# PCB.net
KiCad netlist of a schematic drawn in Altium Designer
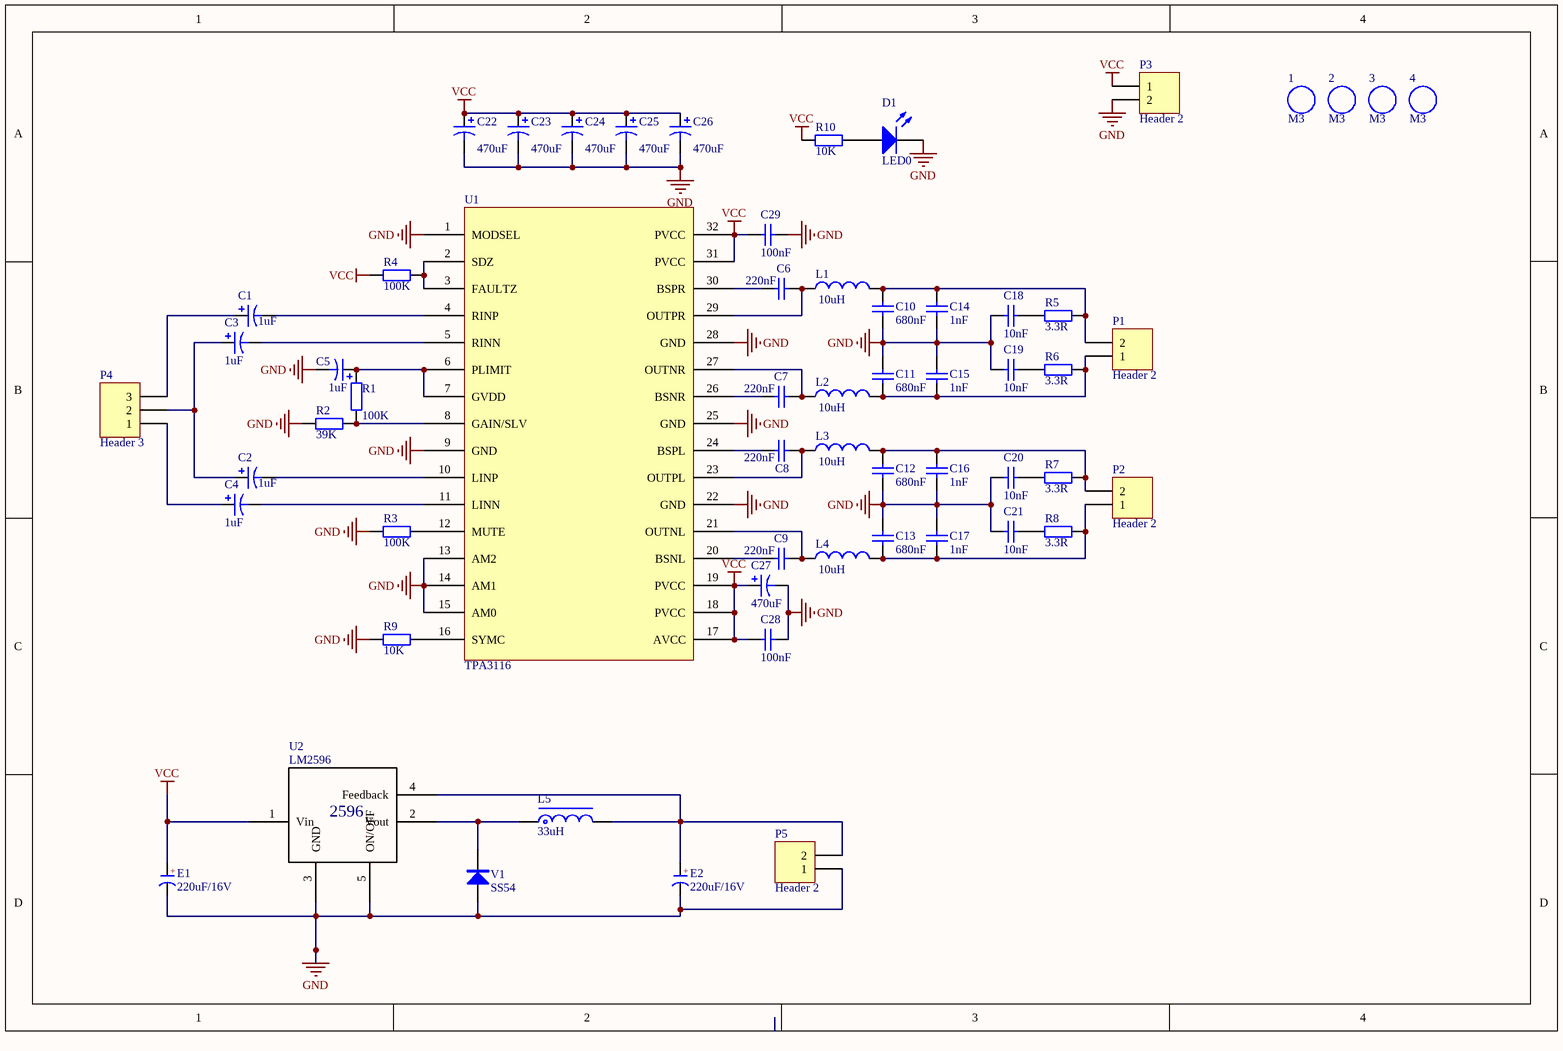
[diagram p0: PCB.SchDoc]

(export (version "E")
  (design (tool "Eeschema 10.0.6"))
  (components
    (comp (ref "1")
      (value "M3")
      (footprint "M3 125X200")
      (description "铜柱孔")
      (fields (field (name "版权归属") "源创客"))
      (libsource (lib "未分类器件") (part "M3"))
    )
    (comp (ref "2")
      (value "M3")
      (footprint "M3 125X200")
      (description "铜柱孔")
      (fields (field (name "版权归属") "源创客"))
      (libsource (lib "未分类器件") (part "M3"))
    )
    (comp (ref "3")
      (value "M3")
      (footprint "M3 125X200")
      (description "铜柱孔")
      (fields (field (name "版权归属") "源创客"))
      (libsource (lib "未分类器件") (part "M3"))
    )
    (comp (ref "4")
      (value "M3")
      (footprint "M3 125X200")
      (description "铜柱孔")
      (fields (field (name "版权归属") "源创客"))
      (libsource (lib "未分类器件") (part "M3"))
    )
    (comp (ref "C1")
      (value "1uF")
      (footprint "C0603")
      (description "Polarized Capacitor (Radial)")
      (fields (field (name "Comment") "Cap Pol1") (field (name "PUBLISHER") "Altium Limited"))
      (libsource (lib "Miscellaneous Devices") (part "Cap Pol1"))
    )
    (comp (ref "C2")
      (value "1uF")
      (footprint "C0603")
      (description "Polarized Capacitor (Radial)")
      (fields (field (name "Comment") "Cap Pol1") (field (name "PUBLISHER") "Altium Limited"))
      (libsource (lib "Miscellaneous Devices") (part "Cap Pol1"))
    )
    (comp (ref "C3")
      (value "1uF")
      (footprint "C0603")
      (description "Polarized Capacitor (Radial)")
      (fields (field (name "Comment") "Cap Pol1") (field (name "PUBLISHER") "Altium Limited"))
      (libsource (lib "Miscellaneous Devices") (part "Cap Pol1"))
    )
    (comp (ref "C4")
      (value "1uF")
      (footprint "C0603")
      (description "Polarized Capacitor (Radial)")
      (fields (field (name "Comment") "Cap Pol1") (field (name "PUBLISHER") "Altium Limited"))
      (libsource (lib "Miscellaneous Devices") (part "Cap Pol1"))
    )
    (comp (ref "C5")
      (value "1uF")
      (footprint "C0603")
      (description "Polarized Capacitor (Radial)")
      (fields (field (name "Comment") "Cap Pol1") (field (name "PUBLISHER") "Altium Limited"))
      (libsource (lib "Miscellaneous Devices") (part "Cap Pol1"))
    )
    (comp (ref "C6")
      (value "220nF")
      (footprint "C0805")
      (description "Capacitor")
      (fields (field (name "Comment") "Cap") (field (name "PUBLISHER") "Altium Limited"))
      (libsource (lib "Miscellaneous Devices") (part "Cap"))
    )
    (comp (ref "C7")
      (value "220nF")
      (footprint "C0805")
      (description "Capacitor")
      (fields (field (name "Comment") "Cap") (field (name "PUBLISHER") "Altium Limited"))
      (libsource (lib "Miscellaneous Devices") (part "Cap"))
    )
    (comp (ref "C8")
      (value "220nF")
      (footprint "C0805")
      (description "Capacitor")
      (fields (field (name "Comment") "Cap") (field (name "PUBLISHER") "Altium Limited"))
      (libsource (lib "Miscellaneous Devices") (part "Cap"))
    )
    (comp (ref "C9")
      (value "220nF")
      (footprint "C0805")
      (description "Capacitor")
      (fields (field (name "Comment") "Cap") (field (name "PUBLISHER") "Altium Limited"))
      (libsource (lib "Miscellaneous Devices") (part "Cap"))
    )
    (comp (ref "C10")
      (value "680nF")
      (footprint "C0805")
      (description "Capacitor")
      (fields (field (name "Comment") "Cap") (field (name "PUBLISHER") "Altium Limited"))
      (libsource (lib "Miscellaneous Devices") (part "Cap"))
    )
    (comp (ref "C11")
      (value "680nF")
      (footprint "C0805")
      (description "Capacitor")
      (fields (field (name "Comment") "Cap") (field (name "PUBLISHER") "Altium Limited"))
      (libsource (lib "Miscellaneous Devices") (part "Cap"))
    )
    (comp (ref "C12")
      (value "680nF")
      (footprint "C0805")
      (description "Capacitor")
      (fields (field (name "Comment") "Cap") (field (name "PUBLISHER") "Altium Limited"))
      (libsource (lib "Miscellaneous Devices") (part "Cap"))
    )
    (comp (ref "C13")
      (value "680nF")
      (footprint "C0805")
      (description "Capacitor")
      (fields (field (name "Comment") "Cap") (field (name "PUBLISHER") "Altium Limited"))
      (libsource (lib "Miscellaneous Devices") (part "Cap"))
    )
    (comp (ref "C14")
      (value "1nF")
      (footprint "C0603")
      (description "Capacitor")
      (fields (field (name "Comment") "Cap") (field (name "PUBLISHER") "Altium Limited"))
      (libsource (lib "Miscellaneous Devices") (part "Cap"))
    )
    (comp (ref "C15")
      (value "1nF")
      (footprint "C0603")
      (description "Capacitor")
      (fields (field (name "Comment") "Cap") (field (name "PUBLISHER") "Altium Limited"))
      (libsource (lib "Miscellaneous Devices") (part "Cap"))
    )
    (comp (ref "C16")
      (value "1nF")
      (footprint "C0603")
      (description "Capacitor")
      (fields (field (name "Comment") "Cap") (field (name "PUBLISHER") "Altium Limited"))
      (libsource (lib "Miscellaneous Devices") (part "Cap"))
    )
    (comp (ref "C17")
      (value "1nF")
      (footprint "C0603")
      (description "Capacitor")
      (fields (field (name "Comment") "Cap") (field (name "PUBLISHER") "Altium Limited"))
      (libsource (lib "Miscellaneous Devices") (part "Cap"))
    )
    (comp (ref "C18")
      (value "10nF")
      (footprint "C0603")
      (description "Capacitor")
      (fields (field (name "Comment") "Cap") (field (name "PUBLISHER") "Altium Limited"))
      (libsource (lib "Miscellaneous Devices") (part "Cap"))
    )
    (comp (ref "C19")
      (value "10nF")
      (footprint "C0603")
      (description "Capacitor")
      (fields (field (name "Comment") "Cap") (field (name "PUBLISHER") "Altium Limited"))
      (libsource (lib "Miscellaneous Devices") (part "Cap"))
    )
    (comp (ref "C20")
      (value "10nF")
      (footprint "C0603")
      (description "Capacitor")
      (fields (field (name "Comment") "Cap") (field (name "PUBLISHER") "Altium Limited"))
      (libsource (lib "Miscellaneous Devices") (part "Cap"))
    )
    (comp (ref "C21")
      (value "10nF")
      (footprint "C0603")
      (description "Capacitor")
      (fields (field (name "Comment") "Cap") (field (name "PUBLISHER") "Altium Limited"))
      (libsource (lib "Miscellaneous Devices") (part "Cap"))
    )
    (comp (ref "C22")
      (value "470uF")
      (footprint "EC-470/25")
      (description "Polarized Capacitor (Radial)")
      (fields (field (name "Comment") "Cap Pol1") (field (name "PUBLISHER") "Altium Limited"))
      (libsource (lib "Miscellaneous Devices") (part "Cap Pol1"))
    )
    (comp (ref "C23")
      (value "470uF")
      (footprint "EC-470/25")
      (description "Polarized Capacitor (Radial)")
      (fields (field (name "Comment") "Cap Pol1") (field (name "PUBLISHER") "Altium Limited"))
      (libsource (lib "Miscellaneous Devices") (part "Cap Pol1"))
    )
    (comp (ref "C24")
      (value "470uF")
      (footprint "EC-470/25")
      (description "Polarized Capacitor (Radial)")
      (fields (field (name "Comment") "Cap Pol1") (field (name "PUBLISHER") "Altium Limited"))
      (libsource (lib "Miscellaneous Devices") (part "Cap Pol1"))
    )
    (comp (ref "C25")
      (value "470uF")
      (footprint "EC-470/25")
      (description "Polarized Capacitor (Radial)")
      (fields (field (name "Comment") "Cap Pol1") (field (name "PUBLISHER") "Altium Limited"))
      (libsource (lib "Miscellaneous Devices") (part "Cap Pol1"))
    )
    (comp (ref "C26")
      (value "470uF")
      (footprint "EC-470/25")
      (description "Polarized Capacitor (Radial)")
      (fields (field (name "Comment") "Cap Pol1") (field (name "PUBLISHER") "Altium Limited"))
      (libsource (lib "Miscellaneous Devices") (part "Cap Pol1"))
    )
    (comp (ref "C27")
      (value "470uF")
      (footprint "EC-470/25")
      (description "Polarized Capacitor (Radial)")
      (fields (field (name "Comment") "Cap Pol1") (field (name "PUBLISHER") "Altium Limited"))
      (libsource (lib "Miscellaneous Devices") (part "Cap Pol1"))
    )
    (comp (ref "C28")
      (value "100nF")
      (footprint "C0603")
      (description "Capacitor")
      (fields (field (name "Comment") "Cap") (field (name "PUBLISHER") "Altium Limited"))
      (libsource (lib "Miscellaneous Devices") (part "Cap"))
    )
    (comp (ref "C29")
      (value "100nF")
      (footprint "C0603")
      (description "Capacitor")
      (fields (field (name "Comment") "Cap") (field (name "PUBLISHER") "Altium Limited"))
      (libsource (lib "Miscellaneous Devices") (part "Cap"))
    )
    (comp (ref "D1")
      (value "LED0")
      (footprint "D0805")
      (description "Typical INFRARED GaAs LED")
      (fields (field (name "PUBLISHER") "Altium Limited"))
      (libsource (lib "Miscellaneous Devices") (part "LED0"))
    )
    (comp (ref "E1")
      (value "220uF/16V")
      (footprint "CM D(6.3*5.4)")
      (description "贴片电解电容")
      (fields (field (name "版权归属") "源创客"))
      (libsource (lib "电阻-电容-电感") (part "C-CM"))
    )
    (comp (ref "E2")
      (value "220uF/16V")
      (footprint "CM D(6.3*7.7)")
      (description "贴片电解电容")
      (fields (field (name "版权归属") "源创客"))
      (libsource (lib "电阻-电容-电感") (part "C-CM"))
    )
    (comp (ref "L1")
      (value "10uH")
      (footprint "L-12*12mm-S")
      (description "Inductor")
      (fields (field (name "PUBLISHER") "Altium Limited"))
      (libsource (lib "Miscellaneous Devices") (part "Inductor"))
    )
    (comp (ref "L2")
      (value "10uH")
      (footprint "L-12*12mm-S")
      (description "Inductor")
      (fields (field (name "PUBLISHER") "Altium Limited"))
      (libsource (lib "Miscellaneous Devices") (part "Inductor"))
    )
    (comp (ref "L3")
      (value "10uH")
      (footprint "L-12*12mm-S")
      (description "Inductor")
      (fields (field (name "PUBLISHER") "Altium Limited"))
      (libsource (lib "Miscellaneous Devices") (part "Inductor"))
    )
    (comp (ref "L4")
      (value "10uH")
      (footprint "L-12*12mm-S")
      (description "Inductor")
      (fields (field (name "PUBLISHER") "Altium Limited"))
      (libsource (lib "Miscellaneous Devices") (part "Inductor"))
    )
    (comp (ref "L5")
      (value "33uH")
      (footprint "CDRH127")
      (description "功率屏蔽电感")
      (fields (field (name "版权归属") "源创客"))
      (libsource (lib "电阻-电容-电感") (part "L-CDRH"))
    )
    (comp (ref "P1")
      (value "Header 2")
      (footprint "HX5.08-2")
      (description "Header, 2-Pin")
      (fields (field (name "PUBLISHER") "Altium Limited"))
      (libsource (lib "") (part "Header 2_1"))
    )
    (comp (ref "P2")
      (value "Header 2")
      (footprint "HX5.08-2")
      (description "Header, 2-Pin")
      (fields (field (name "PUBLISHER") "Altium Limited"))
      (libsource (lib "") (part "Header 2_1"))
    )
    (comp (ref "P3")
      (value "Header 2")
      (footprint "HX5.08-2")
      (description "Header, 2-Pin")
      (fields (field (name "PUBLISHER") "Altium Limited"))
      (libsource (lib "Miscellaneous Connectors") (part "Header 2"))
    )
    (comp (ref "P4")
      (value "Header 3")
      (footprint "HX2.54-3")
      (description "Header, 3-Pin")
      (fields (field (name "PUBLISHER") "Altium Limited"))
      (libsource (lib "Miscellaneous Connectors") (part "Header 3"))
    )
    (comp (ref "P5")
      (value "Header 2")
      (footprint "HDR1X2")
      (description "Header, 2-Pin")
      (fields (field (name "PUBLISHER") "Altium Limited"))
      (libsource (lib "") (part "Header 2_2"))
    )
    (comp (ref "R1")
      (value "100K")
      (footprint "R0603")
      (description "Resistor")
      (fields (field (name "Comment") "Res2") (field (name "PUBLISHER") "Altium Limited"))
      (libsource (lib "") (part "Res2_2"))
    )
    (comp (ref "R2")
      (value "39K")
      (footprint "R0603")
      (description "Resistor")
      (fields (field (name "Comment") "Res2") (field (name "PUBLISHER") "Altium Limited"))
      (libsource (lib "") (part "Res2_1"))
    )
    (comp (ref "R3")
      (value "100K")
      (footprint "R0603")
      (description "Resistor")
      (fields (field (name "Comment") "Res2") (field (name "PUBLISHER") "Altium Limited"))
      (libsource (lib "Miscellaneous Devices") (part "Res2"))
    )
    (comp (ref "R4")
      (value "100K")
      (footprint "R0603")
      (description "Resistor")
      (fields (field (name "Comment") "Res2") (field (name "PUBLISHER") "Altium Limited"))
      (libsource (lib "") (part "Res2_1"))
    )
    (comp (ref "R5")
      (value "3.3R")
      (footprint "R0603")
      (description "Resistor")
      (fields (field (name "Comment") "Res2") (field (name "PUBLISHER") "Altium Limited"))
      (libsource (lib "Miscellaneous Devices") (part "Res2"))
    )
    (comp (ref "R6")
      (value "3.3R")
      (footprint "R0603")
      (description "Resistor")
      (fields (field (name "Comment") "Res2") (field (name "PUBLISHER") "Altium Limited"))
      (libsource (lib "Miscellaneous Devices") (part "Res2"))
    )
    (comp (ref "R7")
      (value "3.3R")
      (footprint "R0603")
      (description "Resistor")
      (fields (field (name "Comment") "Res2") (field (name "PUBLISHER") "Altium Limited"))
      (libsource (lib "") (part "Res2_1"))
    )
    (comp (ref "R8")
      (value "3.3R")
      (footprint "R0603")
      (description "Resistor")
      (fields (field (name "Comment") "Res2") (field (name "PUBLISHER") "Altium Limited"))
      (libsource (lib "") (part "Res2_1"))
    )
    (comp (ref "R9")
      (value "10K")
      (footprint "R0603")
      (description "Resistor")
      (fields (field (name "Comment") "Res2") (field (name "PUBLISHER") "Altium Limited"))
      (libsource (lib "Miscellaneous Devices") (part "Res2"))
    )
    (comp (ref "R10")
      (value "10K")
      (footprint "R0603")
      (description "Resistor")
      (fields (field (name "Comment") "Res2") (field (name "PUBLISHER") "Altium Limited"))
      (libsource (lib "Miscellaneous Devices") (part "Res2"))
    )
    (comp (ref "U1") (value "TPA3116") (footprint "HTSSOP32") (libsource (lib "MySCHLib") (part "TPA3116")))
    (comp (ref "U2")
      (value "LM2596")
      (footprint "LM2596")
      (libsource (lib "Multicoloredstone's_IC_Lib") (part "LM2596"))
    )
    (comp (ref "V1")
      (value "SS54")
      (footprint "SMB")
      (description "肖特基二极管")
      (fields (field (name "版权归属") "源创客"))
      (libsource (lib "二极管-整流桥") (part "SS24"))
    )
  )
  (nets
    (net (code "1") (name "GND") (class "Default")
      (node (ref "C10") (pin "1") (pinfunction "1_1") (pintype "passive"))
      (node (ref "C11") (pin "2") (pinfunction "2_2") (pintype "passive"))
      (node (ref "C12") (pin "1") (pinfunction "1_1") (pintype "passive"))
      (node (ref "C13") (pin "2") (pinfunction "2_2") (pintype "passive"))
      (node (ref "C14") (pin "1") (pinfunction "1_1") (pintype "passive"))
      (node (ref "C15") (pin "2") (pinfunction "2_2") (pintype "passive"))
      (node (ref "C16") (pin "1") (pinfunction "1_1") (pintype "passive"))
      (node (ref "C17") (pin "2") (pinfunction "2_2") (pintype "passive"))
      (node (ref "C18") (pin "2") (pinfunction "2_2") (pintype "passive"))
      (node (ref "C19") (pin "2") (pinfunction "2_2") (pintype "passive"))
      (node (ref "C20") (pin "1") (pinfunction "1_1") (pintype "passive"))
      (node (ref "C21") (pin "1") (pinfunction "1_1") (pintype "passive"))
      (node (ref "C22") (pin "2") (pinfunction "2_2") (pintype "passive"))
      (node (ref "C23") (pin "2") (pinfunction "2_2") (pintype "passive"))
      (node (ref "C24") (pin "2") (pinfunction "2_2") (pintype "passive"))
      (node (ref "C25") (pin "2") (pinfunction "2_2") (pintype "passive"))
      (node (ref "C26") (pin "2") (pinfunction "2_2") (pintype "passive"))
      (node (ref "C27") (pin "2") (pinfunction "2_2") (pintype "passive"))
      (node (ref "C28") (pin "1") (pinfunction "1_1") (pintype "passive"))
      (node (ref "C29") (pin "1") (pinfunction "1_1") (pintype "passive"))
      (node (ref "C5") (pin "2") (pinfunction "2_2") (pintype "passive"))
      (node (ref "D1") (pin "2") (pinfunction "K_2") (pintype "passive"))
      (node (ref "E1") (pin "2") (pinfunction "K_2") (pintype "passive"))
      (node (ref "E2") (pin "2") (pinfunction "K_2") (pintype "passive"))
      (node (ref "P3") (pin "2") (pinfunction "2_2") (pintype "passive"))
      (node (ref "P5") (pin "1") (pinfunction "1_1") (pintype "passive"))
      (node (ref "R2") (pin "2") (pinfunction "2_2") (pintype "passive"))
      (node (ref "R3") (pin "1") (pinfunction "1_1") (pintype "passive"))
      (node (ref "R9") (pin "1") (pinfunction "1_1") (pintype "passive"))
      (node (ref "U1") (pin "1") (pinfunction "MODSEL_1") (pintype "passive"))
      (node (ref "U1") (pin "13") (pinfunction "AM2_13") (pintype "passive"))
      (node (ref "U1") (pin "14") (pinfunction "AM1_14") (pintype "passive"))
      (node (ref "U1") (pin "15") (pinfunction "AM0_15") (pintype "passive"))
      (node (ref "U1") (pin "22") (pinfunction "GND_22") (pintype "passive"))
      (node (ref "U1") (pin "25") (pinfunction "GND_25") (pintype "passive"))
      (node (ref "U1") (pin "28") (pinfunction "GND_28") (pintype "passive"))
      (node (ref "U1") (pin "9") (pinfunction "GND_9") (pintype "passive"))
      (node (ref "U2") (pin "3") (pinfunction "GND_3") (pintype "passive"))
      (node (ref "U2") (pin "5") (pinfunction "ON/OFF_5") (pintype "passive"))
      (node (ref "V1") (pin "1") (pinfunction "A_1") (pintype "passive"))
    )
    (net (code "2") (name "Net-(C1-Pad1)") (class "Default")
      (node (ref "C1") (pin "1") (pinfunction "1_1") (pintype "passive"))
      (node (ref "P4") (pin "3") (pinfunction "3_3") (pintype "passive"))
    )
    (net (code "3") (name "Net-(C2-Pad1)") (class "Default")
      (node (ref "C2") (pin "1") (pinfunction "1_1") (pintype "passive"))
      (node (ref "C3") (pin "1") (pinfunction "1_1") (pintype "passive"))
      (node (ref "P4") (pin "2") (pinfunction "2_2") (pintype "passive"))
    )
    (net (code "4") (name "Net-(C4-Pad1)") (class "Default")
      (node (ref "C4") (pin "1") (pinfunction "1_1") (pintype "passive"))
      (node (ref "P4") (pin "1") (pinfunction "1_1") (pintype "passive"))
    )
    (net (code "5") (name "Net-(C10-Pad2)") (class "Default")
      (node (ref "C10") (pin "2") (pinfunction "2_2") (pintype "passive"))
      (node (ref "C14") (pin "2") (pinfunction "2_2") (pintype "passive"))
      (node (ref "L1") (pin "2") (pinfunction "2_2") (pintype "passive"))
      (node (ref "P1") (pin "2") (pinfunction "2_2") (pintype "passive"))
      (node (ref "R5") (pin "2") (pinfunction "2_2") (pintype "passive"))
    )
    (net (code "6") (name "Net-(C11-Pad1)") (class "Default")
      (node (ref "C11") (pin "1") (pinfunction "1_1") (pintype "passive"))
      (node (ref "C15") (pin "1") (pinfunction "1_1") (pintype "passive"))
      (node (ref "L2") (pin "2") (pinfunction "2_2") (pintype "passive"))
      (node (ref "P1") (pin "1") (pinfunction "1_1") (pintype "passive"))
      (node (ref "R6") (pin "2") (pinfunction "2_2") (pintype "passive"))
    )
    (net (code "7") (name "Net-(C12-Pad2)") (class "Default")
      (node (ref "C12") (pin "2") (pinfunction "2_2") (pintype "passive"))
      (node (ref "C16") (pin "2") (pinfunction "2_2") (pintype "passive"))
      (node (ref "L3") (pin "2") (pinfunction "2_2") (pintype "passive"))
      (node (ref "P2") (pin "2") (pinfunction "2_2") (pintype "passive"))
      (node (ref "R7") (pin "1") (pinfunction "1_1") (pintype "passive"))
    )
    (net (code "8") (name "Net-(C13-Pad1)") (class "Default")
      (node (ref "C13") (pin "1") (pinfunction "1_1") (pintype "passive"))
      (node (ref "C17") (pin "1") (pinfunction "1_1") (pintype "passive"))
      (node (ref "L4") (pin "2") (pinfunction "2_2") (pintype "passive"))
      (node (ref "P2") (pin "1") (pinfunction "1_1") (pintype "passive"))
      (node (ref "R8") (pin "1") (pinfunction "1_1") (pintype "passive"))
    )
    (net (code "9") (name "Net-(C18-Pad1)") (class "Default")
      (node (ref "C18") (pin "1") (pinfunction "1_1") (pintype "passive"))
      (node (ref "R5") (pin "1") (pinfunction "1_1") (pintype "passive"))
    )
    (net (code "10") (name "Net-(C19-Pad1)") (class "Default")
      (node (ref "C19") (pin "1") (pinfunction "1_1") (pintype "passive"))
      (node (ref "R6") (pin "1") (pinfunction "1_1") (pintype "passive"))
    )
    (net (code "11") (name "Net-(C20-Pad2)") (class "Default")
      (node (ref "C20") (pin "2") (pinfunction "2_2") (pintype "passive"))
      (node (ref "R7") (pin "2") (pinfunction "2_2") (pintype "passive"))
    )
    (net (code "12") (name "Net-(C21-Pad2)") (class "Default")
      (node (ref "C21") (pin "2") (pinfunction "2_2") (pintype "passive"))
      (node (ref "R8") (pin "2") (pinfunction "2_2") (pintype "passive"))
    )
    (net (code "13") (name "Net-(D1-A)") (class "Default")
      (node (ref "D1") (pin "1") (pinfunction "A_1") (pintype "passive"))
      (node (ref "R10") (pin "2") (pinfunction "2_2") (pintype "passive"))
    )
    (net (code "14") (name "Net-(E2-A)") (class "Default")
      (node (ref "E2") (pin "1") (pinfunction "A_1") (pintype "passive"))
      (node (ref "L5") (pin "2") (pinfunction "2_2") (pintype "passive"))
      (node (ref "P5") (pin "2") (pinfunction "2_2") (pintype "passive"))
      (node (ref "U2") (pin "4") (pinfunction "Feedback_4") (pintype "passive"))
    )
    (net (code "15") (name "Net-(U1-BSNL)") (class "Default")
      (node (ref "C9") (pin "1") (pinfunction "1_1") (pintype "passive"))
      (node (ref "U1") (pin "20") (pinfunction "BSNL_20") (pintype "passive"))
    )
    (net (code "16") (name "Net-(U1-BSNR)") (class "Default")
      (node (ref "C7") (pin "1") (pinfunction "1_1") (pintype "passive"))
      (node (ref "U1") (pin "26") (pinfunction "BSNR_26") (pintype "passive"))
    )
    (net (code "17") (name "Net-(U1-BSPL)") (class "Default")
      (node (ref "C8") (pin "1") (pinfunction "1_1") (pintype "passive"))
      (node (ref "U1") (pin "24") (pinfunction "BSPL_24") (pintype "passive"))
    )
    (net (code "18") (name "Net-(U1-BSPR)") (class "Default")
      (node (ref "C6") (pin "1") (pinfunction "1_1") (pintype "passive"))
      (node (ref "U1") (pin "30") (pinfunction "BSPR_30") (pintype "passive"))
    )
    (net (code "19") (name "Net-(U1-FAULTZ)") (class "Default")
      (node (ref "R4") (pin "1") (pinfunction "1_1") (pintype "passive"))
      (node (ref "U1") (pin "2") (pinfunction "SDZ_2") (pintype "passive"))
      (node (ref "U1") (pin "3") (pinfunction "FAULTZ_3") (pintype "passive"))
    )
    (net (code "20") (name "Net-(U1-GAIN{slash}SLV)") (class "Default")
      (node (ref "R1") (pin "1") (pinfunction "1_1") (pintype "passive"))
      (node (ref "R2") (pin "1") (pinfunction "1_1") (pintype "passive"))
      (node (ref "U1") (pin "8") (pinfunction "GAIN/SLV_8") (pintype "passive"))
    )
    (net (code "21") (name "Net-(U1-GVDD)") (class "Default")
      (node (ref "C5") (pin "1") (pinfunction "1_1") (pintype "passive"))
      (node (ref "R1") (pin "2") (pinfunction "2_2") (pintype "passive"))
      (node (ref "U1") (pin "6") (pinfunction "PLIMIT_6") (pintype "passive"))
      (node (ref "U1") (pin "7") (pinfunction "GVDD_7") (pintype "passive"))
    )
    (net (code "22") (name "Net-(U1-LINN)") (class "Default")
      (node (ref "C4") (pin "2") (pinfunction "2_2") (pintype "passive"))
      (node (ref "U1") (pin "11") (pinfunction "LINN_11") (pintype "passive"))
    )
    (net (code "23") (name "Net-(U1-LINP)") (class "Default")
      (node (ref "C2") (pin "2") (pinfunction "2_2") (pintype "passive"))
      (node (ref "U1") (pin "10") (pinfunction "LINP_10") (pintype "passive"))
    )
    (net (code "24") (name "Net-(U1-MUTE)") (class "Default")
      (node (ref "R3") (pin "2") (pinfunction "2_2") (pintype "passive"))
      (node (ref "U1") (pin "12") (pinfunction "MUTE_12") (pintype "passive"))
    )
    (net (code "25") (name "Net-(U1-OUTNL)") (class "Default")
      (node (ref "C9") (pin "2") (pinfunction "2_2") (pintype "passive"))
      (node (ref "L4") (pin "1") (pinfunction "1_1") (pintype "passive"))
      (node (ref "U1") (pin "21") (pinfunction "OUTNL_21") (pintype "passive"))
    )
    (net (code "26") (name "Net-(U1-OUTNR)") (class "Default")
      (node (ref "C7") (pin "2") (pinfunction "2_2") (pintype "passive"))
      (node (ref "L2") (pin "1") (pinfunction "1_1") (pintype "passive"))
      (node (ref "U1") (pin "27") (pinfunction "OUTNR_27") (pintype "passive"))
    )
    (net (code "27") (name "Net-(U1-OUTPL)") (class "Default")
      (node (ref "C8") (pin "2") (pinfunction "2_2") (pintype "passive"))
      (node (ref "L3") (pin "1") (pinfunction "1_1") (pintype "passive"))
      (node (ref "U1") (pin "23") (pinfunction "OUTPL_23") (pintype "passive"))
    )
    (net (code "28") (name "Net-(U1-OUTPR)") (class "Default")
      (node (ref "C6") (pin "2") (pinfunction "2_2") (pintype "passive"))
      (node (ref "L1") (pin "1") (pinfunction "1_1") (pintype "passive"))
      (node (ref "U1") (pin "29") (pinfunction "OUTPR_29") (pintype "passive"))
    )
    (net (code "29") (name "Net-(U1-RINN)") (class "Default")
      (node (ref "C3") (pin "2") (pinfunction "2_2") (pintype "passive"))
      (node (ref "U1") (pin "5") (pinfunction "RINN_5") (pintype "passive"))
    )
    (net (code "30") (name "Net-(U1-RINP)") (class "Default")
      (node (ref "C1") (pin "2") (pinfunction "2_2") (pintype "passive"))
      (node (ref "U1") (pin "4") (pinfunction "RINP_4") (pintype "passive"))
    )
    (net (code "31") (name "Net-(U1-SYMC)") (class "Default")
      (node (ref "R9") (pin "2") (pinfunction "2_2") (pintype "passive"))
      (node (ref "U1") (pin "16") (pinfunction "SYMC_16") (pintype "passive"))
    )
    (net (code "32") (name "Net-(U2-Vout)") (class "Default")
      (node (ref "L5") (pin "1") (pinfunction "1_1") (pintype "passive"))
      (node (ref "U2") (pin "2") (pinfunction "Vout_2") (pintype "passive"))
      (node (ref "V1") (pin "2") (pinfunction "K_2") (pintype "passive"))
    )
    (net (code "33") (name "VCC") (class "Default")
      (node (ref "C22") (pin "1") (pinfunction "1_1") (pintype "passive"))
      (node (ref "C23") (pin "1") (pinfunction "1_1") (pintype "passive"))
      (node (ref "C24") (pin "1") (pinfunction "1_1") (pintype "passive"))
      (node (ref "C25") (pin "1") (pinfunction "1_1") (pintype "passive"))
      (node (ref "C26") (pin "1") (pinfunction "1_1") (pintype "passive"))
      (node (ref "C27") (pin "1") (pinfunction "1_1") (pintype "passive"))
      (node (ref "C28") (pin "2") (pinfunction "2_2") (pintype "passive"))
      (node (ref "C29") (pin "2") (pinfunction "2_2") (pintype "passive"))
      (node (ref "E1") (pin "1") (pinfunction "A_1") (pintype "passive"))
      (node (ref "P3") (pin "1") (pinfunction "1_1") (pintype "passive"))
      (node (ref "R10") (pin "1") (pinfunction "1_1") (pintype "passive"))
      (node (ref "R4") (pin "2") (pinfunction "2_2") (pintype "passive"))
      (node (ref "U1") (pin "17") (pinfunction "AVCC_17") (pintype "passive"))
      (node (ref "U1") (pin "18") (pinfunction "PVCC_18") (pintype "passive"))
      (node (ref "U1") (pin "19") (pinfunction "PVCC_19") (pintype "passive"))
      (node (ref "U1") (pin "31") (pinfunction "PVCC_31") (pintype "passive"))
      (node (ref "U1") (pin "32") (pinfunction "PVCC_32") (pintype "passive"))
      (node (ref "U2") (pin "1") (pinfunction "Vin_1") (pintype "passive"))
    )
  )
)
